# 1-Controller.net
KiCad netlist of a schematic drawn in Altium Designer
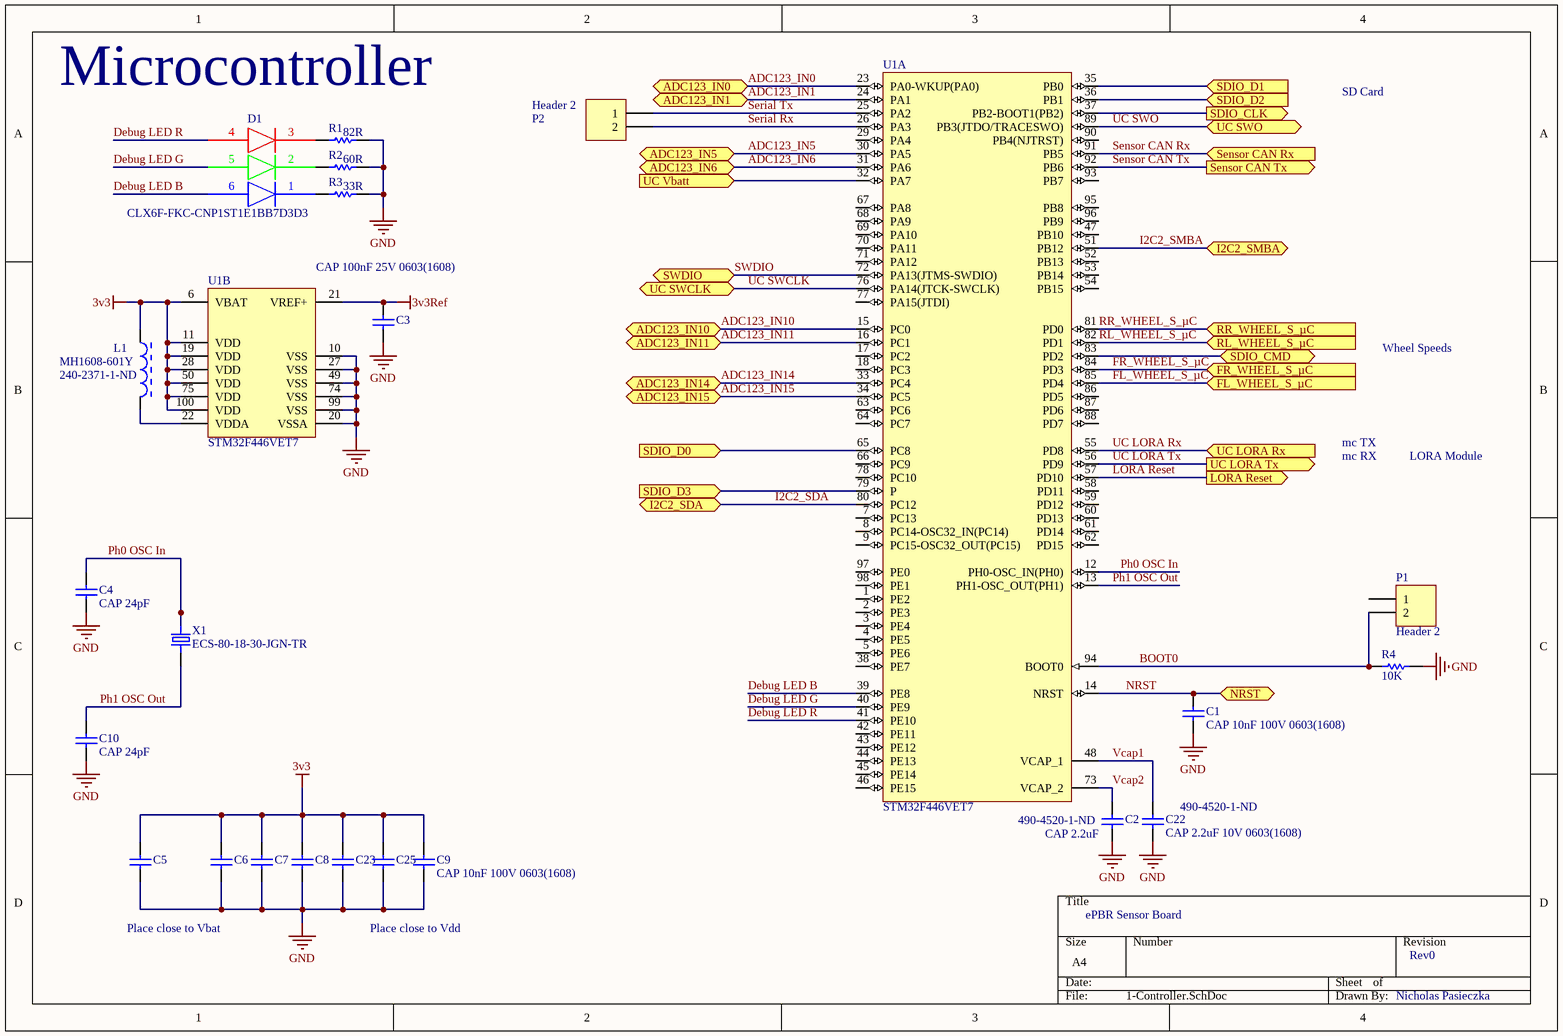
[diagram p0: 1-Controller.SchDoc]

(export (version "E")
  (design (tool "Eeschema 10.0.6"))
  (components
    (comp (ref "C1")
      (value "CAP 10nF 100V 0603(1608)")
      (footprint "CAPC0603(1608)100_M")
      (description "CAP 10nF 100V ±20% 0603 (1608 Metric) Thickness 1mm SMD")
      (fields (field (name "TOLERANCE") "Â±20%"))
      (libsource (lib "ECS-80-18-30-JGN-TR") (part "CAP"))
    )
    (comp (ref "C2")
      (value "CAP 2.2uF")
      (footprint "CAPC0603(1608)55_N")
      (description "CAP 2.2uF 10V ±10% 0603 (1608 Metric) Thickness 0.55mm SMD")
      (fields (field (name "TOLERANCE") "Â±10%") (field (name "SUPPLIER PART NUMBER 1") "490-4520-1-ND"))
      (libsource (lib "Altium Content Vault") (part "CAP"))
    )
    (comp (ref "C3")
      (value "CAP 100nF 25V 0603(1608)")
      (footprint "CAPC0603(1608)100_N")
      (description "CAP 100nF 25V ±20% 0603 (1608 Metric) Thickness 1mm SMD")
      (fields (field (name "TOLERANCE") "Â±20%"))
      (libsource (lib "Altium Content Vault") (part "CAP"))
    )
    (comp (ref "C4")
      (value "CAP 24pF")
      (footprint "CAPC0603(1608)100_N")
      (description "CAP 24pF 16V ±2% 0603 (1608 Metric) Thickness 1mm SMD")
      (fields (field (name "TOLERANCE") "Â±2%"))
      (libsource (lib "Altium Content Vault") (part "CAP"))
    )
    (comp (ref "C5")
      (value "CAP 10nF 100V 0603(1608)")
      (footprint "CAPC0603(1608)100_M")
      (description "CAP 10nF 100V ±20% 0603 (1608 Metric) Thickness 1mm SMD")
      (fields (field (name "TOLERANCE") "Â±20%"))
      (libsource (lib "Altium Content Vault") (part "CAP"))
    )
    (comp (ref "C6")
      (value "CAP 10nF 100V 0603(1608)")
      (footprint "CAPC0603(1608)100_M")
      (description "CAP 10nF 100V ±20% 0603 (1608 Metric) Thickness 1mm SMD")
      (fields (field (name "TOLERANCE") "Â±20%"))
      (libsource (lib "Altium Content Vault") (part "CAP"))
    )
    (comp (ref "C7")
      (value "CAP 10nF 100V 0603(1608)")
      (footprint "CAPC0603(1608)100_M")
      (description "CAP 10nF 100V ±20% 0603 (1608 Metric) Thickness 1mm SMD")
      (fields (field (name "TOLERANCE") "Â±20%"))
      (libsource (lib "Altium Content Vault") (part "CAP"))
    )
    (comp (ref "C8")
      (value "CAP 10nF 100V 0603(1608)")
      (footprint "CAPC0603(1608)100_M")
      (description "CAP 10nF 100V ±20% 0603 (1608 Metric) Thickness 1mm SMD")
      (fields (field (name "TOLERANCE") "Â±20%"))
      (libsource (lib "Altium Content Vault") (part "CAP"))
    )
    (comp (ref "C9")
      (value "CAP 10nF 100V 0603(1608)")
      (footprint "CAPC0603(1608)100_M")
      (description "CAP 10nF 100V ±20% 0603 (1608 Metric) Thickness 1mm SMD")
      (fields (field (name "TOLERANCE") "Â±20%"))
      (libsource (lib "Altium Content Vault") (part "CAP"))
    )
    (comp (ref "C10")
      (value "CAP 24pF")
      (footprint "CAPC0603(1608)100_N")
      (description "CAP 24pF 16V ±2% 0603 (1608 Metric) Thickness 1mm SMD")
      (fields (field (name "TOLERANCE") "Â±2%"))
      (libsource (lib "Altium Content Vault") (part "CAP"))
    )
    (comp (ref "C22")
      (value "CAP 2.2uF 10V 0603(1608)")
      (footprint "CAPC0603(1608)55_N")
      (description "CAP 2.2uF 10V ±10% 0603 (1608 Metric) Thickness 0.55mm SMD")
      (fields (field (name "TOLERANCE") "Â±10%") (field (name "SUPPLIER PART NUMBER 1") "490-4520-1-ND"))
      (libsource (lib "Altium Content Vault") (part "CAP"))
    )
    (comp (ref "C23")
      (value "CAP 10nF 100V 0603(1608)")
      (footprint "CAPC0603(1608)100_M")
      (description "CAP 10nF 100V ±20% 0603 (1608 Metric) Thickness 1mm SMD")
      (fields (field (name "TOLERANCE") "Â±20%"))
      (libsource (lib "Altium Content Vault") (part "CAP"))
    )
    (comp (ref "C25")
      (value "CAP 10nF 100V 0603(1608)")
      (footprint "CAPC0603(1608)100_M")
      (description "CAP 10nF 100V ±20% 0603 (1608 Metric) Thickness 1mm SMD")
      (fields (field (name "TOLERANCE") "Â±20%"))
      (libsource (lib "Altium Content Vault") (part "CAP"))
    )
    (comp (ref "D1")
      (value "CLX6F-FKC-CNP1ST1E1BB7D3D3")
      (footprint "CLX6C-FKB")
      (libsource (lib "VCB_2019") (part "LED - CLX6F-FKC-CNP1ST1E1BB7D3D3"))
    )
    (comp (ref "L1")
      (value "MH1608-601Y")
      (footprint "BOUR-MH1608_V")
      (description "Chip Bead, 600 Ohm, 1 A, -55 to 125 degC, 2-Pin SMD (0603), RoHS, Tape and Reel")
      (fields (field (name "MANUFACTURER") "Bourns") (field (name "SUPPLIER PART NUMBER 1") "240-2371-1-ND"))
      (libsource (lib "Altium Content Vault") (part "IND-FB-2"))
    )
    (comp (ref "P1")
      (value "Header 2")
      (footprint "HDR1X2")
      (description "Header, 2-Pin")
      (fields (field (name "PUBLISHER") "Altium Limited"))
      (libsource (lib "Miscellaneous Connectors") (part "Header 2"))
    )
    (comp (ref "P2")
      (value "Header 2")
      (footprint "HDR1X2")
      (description "Header, 2-Pin")
      (fields (field (name "PUBLISHER") "Altium Limited"))
      (libsource (lib "") (part "Header 2_1"))
    )
    (comp (ref "R1")
      (value "82R")
      (footprint "RESC0603(1608)_N")
      (description "82R 0.1W 5% 0603 (1608 Metric)  SMD")
      (fields (field (name "TOLERANCE") "5 %") (field (name "POWER") "0.1 W"))
      (libsource (lib "Altium Content Vault") (part "RES"))
    )
    (comp (ref "R2")
      (value "60R")
      (footprint "RESC0603(1608)_N")
      (description "60R4 0.1W 1% 0603 (1608 Metric)  SMD")
      (fields (field (name "TOLERANCE") "1 %") (field (name "POWER") "0.1 W"))
      (libsource (lib "Altium Content Vault") (part "RES"))
    )
    (comp (ref "R3")
      (value "33R")
      (footprint "RESC0603(1608)_N")
      (description "33R 0.1W 5% 0603 (1608 Metric)  SMD")
      (fields (field (name "TOLERANCE") "5 %") (field (name "POWER") "0.1 W"))
      (libsource (lib "Altium Content Vault") (part "RES"))
    )
    (comp (ref "R4")
      (value "10K")
      (footprint "RESC0603(1608)_N")
      (description "10K 0.1W 5% 0603 (1608 Metric)  SMD")
      (fields (field (name "TOLERANCE") "5 %") (field (name "POWER") "0.1 W"))
      (libsource (lib "Altium Content Vault") (part "RES"))
    )
    (comp (ref "U1")
      (value "STM32F446VET7")
      (footprint "STM-LQFP100_L")
      (libsource (lib "Altium Content Vault") (part "MC-ARM-STM32F446-LQFP100"))
    )
    (comp (ref "X1")
      (value "ECS-80-18-30-JGN-TR")
      (footprint "SnapEDApcb:XTAL_ECS-80-18-30-JGN-TR")
      (description "8MHz Â±20ppm Crystal 18pF 100 Ohms 2-SMD, No Lead")
      (fields (field (name "DIGI-KEY_PART_NUMBER") "XC2103CT-ND") (field (name "MF") "ECS Inc."))
      (libsource (lib "SnapEDAsch") (part "ECS-80-18-30-JGN-TR"))
    )
  )
  (nets
    (net (code "1") (name "/ADC123_IN0") (class "Default")
      (node (ref "U1") (pin "23") (pinfunction "PA0-WKUP(PA0)_23") (pintype "bidirectional"))
    )
    (net (code "2") (name "/ADC123_IN1") (class "Default")
      (node (ref "U1") (pin "24") (pinfunction "PA1_24") (pintype "bidirectional"))
    )
    (net (code "3") (name "/ADC123_IN5") (class "Default")
      (node (ref "U1") (pin "30") (pinfunction "PA5_30") (pintype "bidirectional"))
    )
    (net (code "4") (name "/ADC123_IN6") (class "Default")
      (node (ref "U1") (pin "31") (pinfunction "PA6_31") (pintype "bidirectional"))
    )
    (net (code "5") (name "/ADC123_IN10") (class "Default")
      (node (ref "U1") (pin "15") (pinfunction "PC0_15") (pintype "bidirectional"))
    )
    (net (code "6") (name "/ADC123_IN11") (class "Default")
      (node (ref "U1") (pin "16") (pinfunction "PC1_16") (pintype "bidirectional"))
    )
    (net (code "7") (name "/ADC123_IN14") (class "Default")
      (node (ref "U1") (pin "33") (pinfunction "PC4_33") (pintype "bidirectional"))
    )
    (net (code "8") (name "/ADC123_IN15") (class "Default")
      (node (ref "U1") (pin "34") (pinfunction "PC5_34") (pintype "bidirectional"))
    )
    (net (code "9") (name "/BOOT0") (class "Default")
      (node (ref "P1") (pin "2") (pinfunction "2_2") (pintype "passive"))
      (node (ref "R4") (pin "1") (pinfunction "1_1") (pintype "passive"))
      (node (ref "U1") (pin "94") (pinfunction "BOOT0_94") (pintype "input"))
    )
    (net (code "10") (name "/Debug LED B") (class "Default")
      (node (ref "D1") (pin "6") (pinfunction "B_6") (pintype "passive"))
      (node (ref "U1") (pin "39") (pinfunction "PE8_39") (pintype "bidirectional"))
    )
    (net (code "11") (name "/Debug LED G") (class "Default")
      (node (ref "D1") (pin "5") (pinfunction "G_5") (pintype "passive"))
      (node (ref "U1") (pin "40") (pinfunction "PE9_40") (pintype "bidirectional"))
    )
    (net (code "12") (name "/Debug LED R") (class "Default")
      (node (ref "D1") (pin "4") (pinfunction "R_4") (pintype "passive"))
      (node (ref "U1") (pin "41") (pinfunction "PE10_41") (pintype "bidirectional"))
    )
    (net (code "13") (name "/FL_WHEEL_S_µC") (class "Default")
      (node (ref "U1") (pin "85") (pinfunction "PD4_85") (pintype "bidirectional"))
    )
    (net (code "14") (name "/FR_WHEEL_S_µC") (class "Default")
      (node (ref "U1") (pin "84") (pinfunction "PD3_84") (pintype "bidirectional"))
    )
    (net (code "15") (name "/I2C2_SDA") (class "Default")
      (node (ref "U1") (pin "80") (pinfunction "PC12_80") (pintype "bidirectional"))
    )
    (net (code "16") (name "/I2C2_SMBA") (class "Default")
      (node (ref "U1") (pin "51") (pinfunction "PB12_51") (pintype "bidirectional"))
    )
    (net (code "17") (name "/LORA Reset") (class "Default")
      (node (ref "U1") (pin "57") (pinfunction "PD10_57") (pintype "bidirectional"))
    )
    (net (code "18") (name "/NRST") (class "Default")
      (node (ref "C1") (pin "2") (pinfunction "2_2") (pintype "passive"))
      (node (ref "U1") (pin "14") (pinfunction "NRST_14") (pintype "bidirectional"))
    )
    (net (code "19") (name "/Ph0 OSC In") (class "Default")
      (node (ref "C4") (pin "2") (pinfunction "2_2") (pintype "passive"))
      (node (ref "U1") (pin "12") (pinfunction "PH0-OSC_IN(PH0)_12") (pintype "bidirectional"))
      (node (ref "X1") (pin "2") (pinfunction "OUT/IN_2") (pintype "passive"))
    )
    (net (code "20") (name "/Ph1 OSC Out") (class "Default")
      (node (ref "C10") (pin "2") (pinfunction "2_2") (pintype "passive"))
      (node (ref "U1") (pin "13") (pinfunction "PH1-OSC_OUT(PH1)_13") (pintype "bidirectional"))
      (node (ref "X1") (pin "1") (pinfunction "IN/OUT_1") (pintype "passive"))
    )
    (net (code "21") (name "/RL_WHEEL_S_µC") (class "Default")
      (node (ref "U1") (pin "82") (pinfunction "PD1_82") (pintype "bidirectional"))
    )
    (net (code "22") (name "/RR_WHEEL_S_µC") (class "Default")
      (node (ref "U1") (pin "81") (pinfunction "PD0_81") (pintype "bidirectional"))
    )
    (net (code "23") (name "/SDIO_CLK") (class "Default")
      (node (ref "U1") (pin "37") (pinfunction "PB2-BOOT1(PB2)_37") (pintype "bidirectional"))
    )
    (net (code "24") (name "/SDIO_CMD") (class "Default")
      (node (ref "U1") (pin "83") (pinfunction "PD2_83") (pintype "bidirectional"))
    )
    (net (code "25") (name "/SDIO_D0") (class "Default")
      (node (ref "U1") (pin "65") (pinfunction "PC8_65") (pintype "bidirectional"))
    )
    (net (code "26") (name "/SDIO_D1") (class "Default")
      (node (ref "U1") (pin "35") (pinfunction "PB0_35") (pintype "bidirectional"))
    )
    (net (code "27") (name "/SDIO_D2") (class "Default")
      (node (ref "U1") (pin "36") (pinfunction "PB1_36") (pintype "bidirectional"))
    )
    (net (code "28") (name "/SDIO_D3") (class "Default")
      (node (ref "U1") (pin "79") (pinfunction "P_79") (pintype "bidirectional"))
    )
    (net (code "29") (name "/SWDIO") (class "Default")
      (node (ref "U1") (pin "72") (pinfunction "PA13(JTMS-SWDIO)_72") (pintype "bidirectional"))
    )
    (net (code "30") (name "/Sensor CAN Rx") (class "Default")
      (node (ref "U1") (pin "91") (pinfunction "PB5_91") (pintype "bidirectional"))
    )
    (net (code "31") (name "/Sensor CAN Tx") (class "Default")
      (node (ref "U1") (pin "92") (pinfunction "PB6_92") (pintype "bidirectional"))
    )
    (net (code "32") (name "/Serial Rx") (class "Default")
      (node (ref "P2") (pin "2") (pinfunction "2_2") (pintype "passive"))
      (node (ref "U1") (pin "26") (pinfunction "PA3_26") (pintype "bidirectional"))
    )
    (net (code "33") (name "/Serial Tx") (class "Default")
      (node (ref "P2") (pin "1") (pinfunction "1_1") (pintype "passive"))
      (node (ref "U1") (pin "25") (pinfunction "PA2_25") (pintype "bidirectional"))
    )
    (net (code "34") (name "/UC LORA Rx") (class "Default")
      (node (ref "U1") (pin "55") (pinfunction "PD8_55") (pintype "bidirectional"))
    )
    (net (code "35") (name "/UC LORA Tx") (class "Default")
      (node (ref "U1") (pin "56") (pinfunction "PD9_56") (pintype "bidirectional"))
    )
    (net (code "36") (name "/UC SWCLK") (class "Default")
      (node (ref "U1") (pin "76") (pinfunction "PA14(JTCK-SWCLK)_76") (pintype "bidirectional"))
    )
    (net (code "37") (name "/UC SWO") (class "Default")
      (node (ref "U1") (pin "89") (pinfunction "PB3(JTDO/TRACESWO)_89") (pintype "bidirectional"))
    )
    (net (code "38") (name "/UC Vbatt") (class "Default")
      (node (ref "U1") (pin "32") (pinfunction "PA7_32") (pintype "bidirectional"))
    )
    (net (code "39") (name "/Vcap1") (class "Default")
      (node (ref "C22") (pin "2") (pinfunction "2_2") (pintype "passive"))
      (node (ref "U1") (pin "48") (pinfunction "VCAP_1_48") (pintype "passive"))
    )
    (net (code "40") (name "/Vcap2") (class "Default")
      (node (ref "C2") (pin "2") (pinfunction "2_2") (pintype "passive"))
      (node (ref "U1") (pin "73") (pinfunction "VCAP_2_73") (pintype "passive"))
    )
    (net (code "41") (name "3v3") (class "Default")
      (node (ref "C23") (pin "2") (pinfunction "2_2") (pintype "passive"))
      (node (ref "C25") (pin "2") (pinfunction "2_2") (pintype "passive"))
      (node (ref "C5") (pin "2") (pinfunction "2_2") (pintype "passive"))
      (node (ref "C6") (pin "2") (pinfunction "2_2") (pintype "passive"))
      (node (ref "C7") (pin "2") (pinfunction "2_2") (pintype "passive"))
      (node (ref "C8") (pin "2") (pinfunction "2_2") (pintype "passive"))
      (node (ref "C9") (pin "2") (pinfunction "2_2") (pintype "passive"))
      (node (ref "L1") (pin "1") (pinfunction "1_1") (pintype "passive"))
      (node (ref "U1") (pin "100") (pinfunction "VDD_100") (pintype "power_in"))
      (node (ref "U1") (pin "11") (pinfunction "VDD_11") (pintype "power_in"))
      (node (ref "U1") (pin "19") (pinfunction "VDD_19") (pintype "power_in"))
      (node (ref "U1") (pin "28") (pinfunction "VDD_28") (pintype "power_in"))
      (node (ref "U1") (pin "50") (pinfunction "VDD_50") (pintype "power_in"))
      (node (ref "U1") (pin "6") (pinfunction "VBAT_6") (pintype "power_in"))
      (node (ref "U1") (pin "75") (pinfunction "VDD_75") (pintype "power_in"))
    )
    (net (code "42") (name "3v3Ref") (class "Default")
      (node (ref "C3") (pin "2") (pinfunction "2_2") (pintype "passive"))
      (node (ref "U1") (pin "21") (pinfunction "VREF+_21") (pintype "power_in"))
    )
    (net (code "43") (name "GND") (class "Default")
      (node (ref "C1") (pin "1") (pinfunction "1_1") (pintype "passive"))
      (node (ref "C10") (pin "1") (pinfunction "1_1") (pintype "passive"))
      (node (ref "C2") (pin "1") (pinfunction "1_1") (pintype "passive"))
      (node (ref "C22") (pin "1") (pinfunction "1_1") (pintype "passive"))
      (node (ref "C23") (pin "1") (pinfunction "1_1") (pintype "passive"))
      (node (ref "C25") (pin "1") (pinfunction "1_1") (pintype "passive"))
      (node (ref "C3") (pin "1") (pinfunction "1_1") (pintype "passive"))
      (node (ref "C4") (pin "1") (pinfunction "1_1") (pintype "passive"))
      (node (ref "C5") (pin "1") (pinfunction "1_1") (pintype "passive"))
      (node (ref "C6") (pin "1") (pinfunction "1_1") (pintype "passive"))
      (node (ref "C7") (pin "1") (pinfunction "1_1") (pintype "passive"))
      (node (ref "C8") (pin "1") (pinfunction "1_1") (pintype "passive"))
      (node (ref "C9") (pin "1") (pinfunction "1_1") (pintype "passive"))
      (node (ref "R1") (pin "2") (pinfunction "2_2") (pintype "passive"))
      (node (ref "R2") (pin "2") (pinfunction "2_2") (pintype "passive"))
      (node (ref "R3") (pin "2") (pinfunction "2_2") (pintype "passive"))
      (node (ref "R4") (pin "2") (pinfunction "2_2") (pintype "passive"))
      (node (ref "U1") (pin "10") (pinfunction "VSS_10") (pintype "power_in"))
      (node (ref "U1") (pin "20") (pinfunction "VSSA_20") (pintype "power_in"))
      (node (ref "U1") (pin "27") (pinfunction "VSS_27") (pintype "power_in"))
      (node (ref "U1") (pin "49") (pinfunction "VSS_49") (pintype "power_in"))
      (node (ref "U1") (pin "74") (pinfunction "VSS_74") (pintype "power_in"))
      (node (ref "U1") (pin "99") (pinfunction "VSS_99") (pintype "power_in"))
    )
    (net (code "44") (name "Net-(D1-B-Pad1)") (class "Default")
      (node (ref "D1") (pin "1") (pinfunction "B_1") (pintype "passive"))
      (node (ref "R3") (pin "1") (pinfunction "1_1") (pintype "passive"))
    )
    (net (code "45") (name "Net-(D1-G-Pad2)") (class "Default")
      (node (ref "D1") (pin "2") (pinfunction "G_2") (pintype "passive"))
      (node (ref "R2") (pin "1") (pinfunction "1_1") (pintype "passive"))
    )
    (net (code "46") (name "Net-(D1-R-Pad3)") (class "Default")
      (node (ref "D1") (pin "3") (pinfunction "R_3") (pintype "passive"))
      (node (ref "R1") (pin "1") (pinfunction "1_1") (pintype "passive"))
    )
    (net (code "47") (name "Net-(U1B-VDDA)") (class "Default")
      (node (ref "L1") (pin "2") (pinfunction "2_2") (pintype "passive"))
      (node (ref "U1") (pin "22") (pinfunction "VDDA_22") (pintype "power_in"))
    )
    (net (code "48") (name "unconnected-(P1-Pad1)") (class "Default")
      (node (ref "P1") (pin "1") (pinfunction "1_1") (pintype "passive"))
    )
    (net (code "49") (name "unconnected-(U1A-PA4-Pad29)") (class "Default")
      (node (ref "U1") (pin "29") (pinfunction "PA4_29") (pintype "bidirectional"))
    )
    (net (code "50") (name "unconnected-(U1A-PA8-Pad67)") (class "Default")
      (node (ref "U1") (pin "67") (pinfunction "PA8_67") (pintype "bidirectional"))
    )
    (net (code "51") (name "unconnected-(U1A-PA9-Pad68)") (class "Default")
      (node (ref "U1") (pin "68") (pinfunction "PA9_68") (pintype "bidirectional"))
    )
    (net (code "52") (name "unconnected-(U1A-PA10-Pad69)") (class "Default")
      (node (ref "U1") (pin "69") (pinfunction "PA10_69") (pintype "bidirectional"))
    )
    (net (code "53") (name "unconnected-(U1A-PA11-Pad70)") (class "Default")
      (node (ref "U1") (pin "70") (pinfunction "PA11_70") (pintype "bidirectional"))
    )
    (net (code "54") (name "unconnected-(U1A-PA12-Pad71)") (class "Default")
      (node (ref "U1") (pin "71") (pinfunction "PA12_71") (pintype "bidirectional"))
    )
    (net (code "55") (name "unconnected-(U1A-PA15(JTDI)-Pad77)") (class "Default")
      (node (ref "U1") (pin "77") (pinfunction "PA15(JTDI)_77") (pintype "bidirectional"))
    )
    (net (code "56") (name "unconnected-(U1A-PB4(NJTRST)-Pad90)") (class "Default")
      (node (ref "U1") (pin "90") (pinfunction "PB4(NJTRST)_90") (pintype "bidirectional"))
    )
    (net (code "57") (name "unconnected-(U1A-PB7-Pad93)") (class "Default")
      (node (ref "U1") (pin "93") (pinfunction "PB7_93") (pintype "bidirectional"))
    )
    (net (code "58") (name "unconnected-(U1A-PB8-Pad95)") (class "Default")
      (node (ref "U1") (pin "95") (pinfunction "PB8_95") (pintype "bidirectional"))
    )
    (net (code "59") (name "unconnected-(U1A-PB9-Pad96)") (class "Default")
      (node (ref "U1") (pin "96") (pinfunction "PB9_96") (pintype "bidirectional"))
    )
    (net (code "60") (name "unconnected-(U1A-PB10-Pad47)") (class "Default")
      (node (ref "U1") (pin "47") (pinfunction "PB10_47") (pintype "bidirectional"))
    )
    (net (code "61") (name "unconnected-(U1A-PB13-Pad52)") (class "Default")
      (node (ref "U1") (pin "52") (pinfunction "PB13_52") (pintype "bidirectional"))
    )
    (net (code "62") (name "unconnected-(U1A-PB14-Pad53)") (class "Default")
      (node (ref "U1") (pin "53") (pinfunction "PB14_53") (pintype "bidirectional"))
    )
    (net (code "63") (name "unconnected-(U1A-PB15-Pad54)") (class "Default")
      (node (ref "U1") (pin "54") (pinfunction "PB15_54") (pintype "bidirectional"))
    )
    (net (code "64") (name "unconnected-(U1A-PC2-Pad17)") (class "Default")
      (node (ref "U1") (pin "17") (pinfunction "PC2_17") (pintype "bidirectional"))
    )
    (net (code "65") (name "unconnected-(U1A-PC3-Pad18)") (class "Default")
      (node (ref "U1") (pin "18") (pinfunction "PC3_18") (pintype "bidirectional"))
    )
    (net (code "66") (name "unconnected-(U1A-PC6-Pad63)") (class "Default")
      (node (ref "U1") (pin "63") (pinfunction "PC6_63") (pintype "bidirectional"))
    )
    (net (code "67") (name "unconnected-(U1A-PC7-Pad64)") (class "Default")
      (node (ref "U1") (pin "64") (pinfunction "PC7_64") (pintype "bidirectional"))
    )
    (net (code "68") (name "unconnected-(U1A-PC9-Pad66)") (class "Default")
      (node (ref "U1") (pin "66") (pinfunction "PC9_66") (pintype "bidirectional"))
    )
    (net (code "69") (name "unconnected-(U1A-PC10-Pad78)") (class "Default")
      (node (ref "U1") (pin "78") (pinfunction "PC10_78") (pintype "bidirectional"))
    )
    (net (code "70") (name "unconnected-(U1A-PC13-Pad7)") (class "Default")
      (node (ref "U1") (pin "7") (pinfunction "PC13_7") (pintype "bidirectional"))
    )
    (net (code "71") (name "unconnected-(U1A-PC14-OSC32_IN(PC14)-Pad8)") (class "Default")
      (node (ref "U1") (pin "8") (pinfunction "PC14-OSC32_IN(PC14)_8") (pintype "bidirectional"))
    )
    (net (code "72") (name "unconnected-(U1A-PC15-OSC32_OUT(PC15)-Pad9)") (class "Default")
      (node (ref "U1") (pin "9") (pinfunction "PC15-OSC32_OUT(PC15)_9") (pintype "bidirectional"))
    )
    (net (code "73") (name "unconnected-(U1A-PD5-Pad86)") (class "Default")
      (node (ref "U1") (pin "86") (pinfunction "PD5_86") (pintype "bidirectional"))
    )
    (net (code "74") (name "unconnected-(U1A-PD6-Pad87)") (class "Default")
      (node (ref "U1") (pin "87") (pinfunction "PD6_87") (pintype "bidirectional"))
    )
    (net (code "75") (name "unconnected-(U1A-PD7-Pad88)") (class "Default")
      (node (ref "U1") (pin "88") (pinfunction "PD7_88") (pintype "bidirectional"))
    )
    (net (code "76") (name "unconnected-(U1A-PD11-Pad58)") (class "Default")
      (node (ref "U1") (pin "58") (pinfunction "PD11_58") (pintype "bidirectional"))
    )
    (net (code "77") (name "unconnected-(U1A-PD12-Pad59)") (class "Default")
      (node (ref "U1") (pin "59") (pinfunction "PD12_59") (pintype "bidirectional"))
    )
    (net (code "78") (name "unconnected-(U1A-PD13-Pad60)") (class "Default")
      (node (ref "U1") (pin "60") (pinfunction "PD13_60") (pintype "bidirectional"))
    )
    (net (code "79") (name "unconnected-(U1A-PD14-Pad61)") (class "Default")
      (node (ref "U1") (pin "61") (pinfunction "PD14_61") (pintype "bidirectional"))
    )
    (net (code "80") (name "unconnected-(U1A-PD15-Pad62)") (class "Default")
      (node (ref "U1") (pin "62") (pinfunction "PD15_62") (pintype "bidirectional"))
    )
    (net (code "81") (name "unconnected-(U1A-PE0-Pad97)") (class "Default")
      (node (ref "U1") (pin "97") (pinfunction "PE0_97") (pintype "bidirectional"))
    )
    (net (code "82") (name "unconnected-(U1A-PE1-Pad98)") (class "Default")
      (node (ref "U1") (pin "98") (pinfunction "PE1_98") (pintype "bidirectional"))
    )
    (net (code "83") (name "unconnected-(U1A-PE2-Pad1)") (class "Default")
      (node (ref "U1") (pin "1") (pinfunction "PE2_1") (pintype "bidirectional"))
    )
    (net (code "84") (name "unconnected-(U1A-PE3-Pad2)") (class "Default")
      (node (ref "U1") (pin "2") (pinfunction "PE3_2") (pintype "bidirectional"))
    )
    (net (code "85") (name "unconnected-(U1A-PE4-Pad3)") (class "Default")
      (node (ref "U1") (pin "3") (pinfunction "PE4_3") (pintype "bidirectional"))
    )
    (net (code "86") (name "unconnected-(U1A-PE5-Pad4)") (class "Default")
      (node (ref "U1") (pin "4") (pinfunction "PE5_4") (pintype "bidirectional"))
    )
    (net (code "87") (name "unconnected-(U1A-PE6-Pad5)") (class "Default")
      (node (ref "U1") (pin "5") (pinfunction "PE6_5") (pintype "bidirectional"))
    )
    (net (code "88") (name "unconnected-(U1A-PE7-Pad38)") (class "Default")
      (node (ref "U1") (pin "38") (pinfunction "PE7_38") (pintype "bidirectional"))
    )
    (net (code "89") (name "unconnected-(U1A-PE11-Pad42)") (class "Default")
      (node (ref "U1") (pin "42") (pinfunction "PE11_42") (pintype "bidirectional"))
    )
    (net (code "90") (name "unconnected-(U1A-PE12-Pad43)") (class "Default")
      (node (ref "U1") (pin "43") (pinfunction "PE12_43") (pintype "bidirectional"))
    )
    (net (code "91") (name "unconnected-(U1A-PE13-Pad44)") (class "Default")
      (node (ref "U1") (pin "44") (pinfunction "PE13_44") (pintype "bidirectional"))
    )
    (net (code "92") (name "unconnected-(U1A-PE14-Pad45)") (class "Default")
      (node (ref "U1") (pin "45") (pinfunction "PE14_45") (pintype "bidirectional"))
    )
    (net (code "93") (name "unconnected-(U1A-PE15-Pad46)") (class "Default")
      (node (ref "U1") (pin "46") (pinfunction "PE15_46") (pintype "bidirectional"))
    )
  )
)
